# Sensor_Board_2_03_HX711_DS18b2.net
KiCad netlist of a schematic drawn in EAGLE
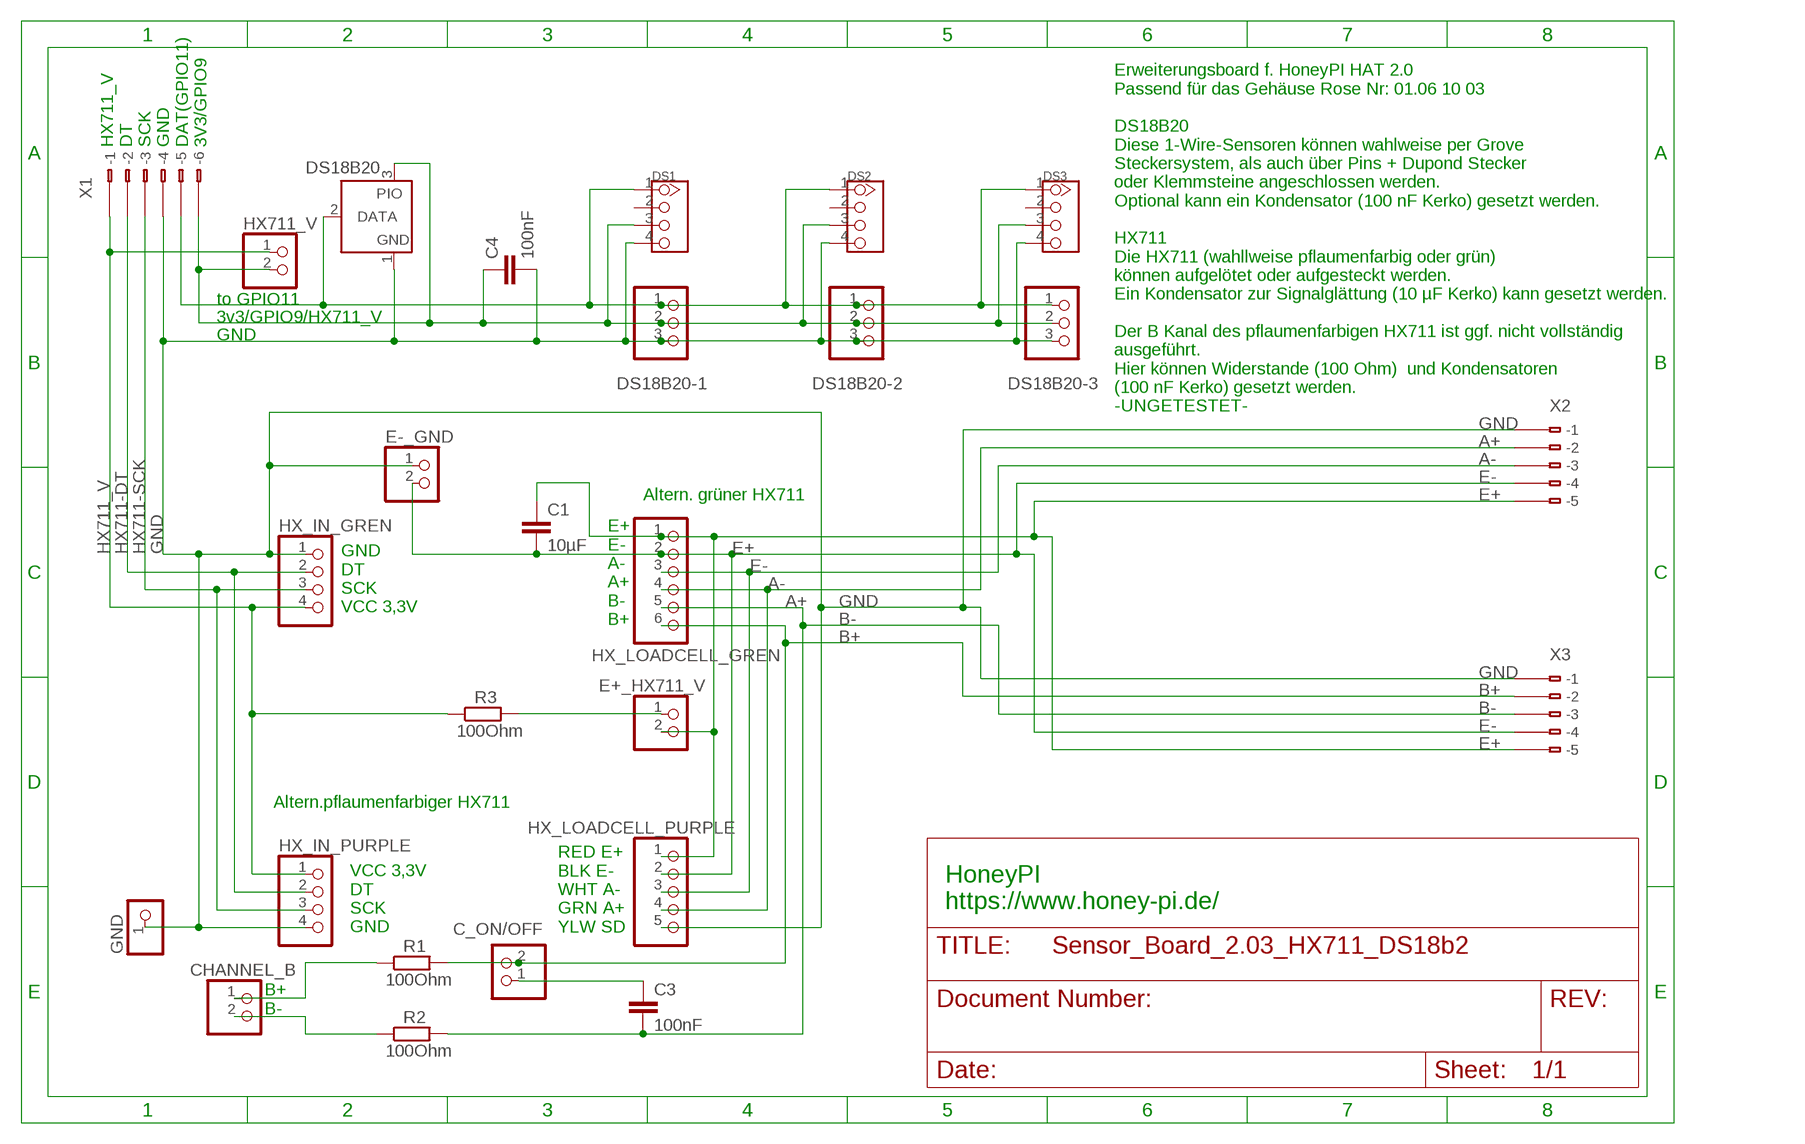
[diagram p0: schematic, sheet 1]

(export (version "E")
  (design (tool "Eeschema 10.0.6"))
  (components
    (comp (ref "C1")
      (value "10µF")
      (footprint "eagle-import:C5B2.5")
      (libsource (lib "eagle-import") (part "C5/2.5"))
    )
    (comp (ref "C3")
      (value "100nF")
      (footprint "eagle-import:C5B2.5")
      (libsource (lib "eagle-import") (part "C5/2.5"))
    )
    (comp (ref "C4")
      (value "100nF")
      (footprint "eagle-import:C5B2.5")
      (libsource (lib "eagle-import") (part "C5/2.5"))
    )
    (comp (ref "CHANNEL_B")
      (value "PINHD-1X2")
      (footprint "eagle-import:1X02")
      (libsource (lib "eagle-import") (part "PINHD-1X2"))
    )
    (comp (ref "C_ON/OFF")
      (value "PINHD-1X2")
      (footprint "eagle-import:1X02")
      (libsource (lib "eagle-import") (part "PINHD-1X2"))
    )
    (comp (ref "DS1")
      (value "TWIG-4P-2.0-2.0")
      (footprint "eagle-import:4P-2.0")
      (libsource (lib "eagle-import") (part "TWIG-4P-2.0-2.0"))
    )
    (comp (ref "DS2")
      (value "TWIG-4P-2.0-2.0")
      (footprint "eagle-import:4P-2.0")
      (libsource (lib "eagle-import") (part "TWIG-4P-2.0-2.0"))
    )
    (comp (ref "DS3")
      (value "TWIG-4P-2.0-2.0")
      (footprint "eagle-import:4P-2.0")
      (libsource (lib "eagle-import") (part "TWIG-4P-2.0-2.0"))
    )
    (comp (ref "DS18B20")
      (value "DS2405")
      (footprint "eagle-import:TO92-")
      (fields (field (name "MF") "DALLAS SEMICONDUCTOR"))
      (libsource (lib "eagle-import") (part "DS2405"))
    )
    (comp (ref "DS18B20-1")
      (value "PINHD-1X3")
      (footprint "eagle-import:1X03")
      (libsource (lib "eagle-import") (part "PINHD-1X3"))
    )
    (comp (ref "DS18B20-2")
      (value "PINHD-1X3")
      (footprint "eagle-import:1X03")
      (libsource (lib "eagle-import") (part "PINHD-1X3"))
    )
    (comp (ref "DS18B20-3")
      (value "PINHD-1X3")
      (footprint "eagle-import:1X03")
      (libsource (lib "eagle-import") (part "PINHD-1X3"))
    )
    (comp (ref "E+_HX711_V")
      (value "PINHD-1X2")
      (footprint "eagle-import:1X02")
      (libsource (lib "eagle-import") (part "PINHD-1X2"))
    )
    (comp (ref "E-_GND")
      (value "PINHD-1X2")
      (footprint "eagle-import:1X02")
      (libsource (lib "eagle-import") (part "PINHD-1X2"))
    )
    (comp (ref "GND")
      (value "PINHD-1X1")
      (footprint "eagle-import:1X01")
      (libsource (lib "eagle-import") (part "PINHD-1X1"))
    )
    (comp (ref "HX711_V")
      (value "PINHD-1X2")
      (footprint "eagle-import:1X02")
      (libsource (lib "eagle-import") (part "PINHD-1X2"))
    )
    (comp (ref "HX_IN_GREN")
      (value "PINHD-1X4")
      (footprint "eagle-import:1X04")
      (libsource (lib "eagle-import") (part "PINHD-1X4"))
    )
    (comp (ref "HX_IN_PURPLE")
      (value "PINHD-1X4")
      (footprint "eagle-import:1X04")
      (libsource (lib "eagle-import") (part "PINHD-1X4"))
    )
    (comp (ref "HX_LOADCELL_GREN")
      (value "PINHD-1X6")
      (footprint "eagle-import:1X06")
      (libsource (lib "eagle-import") (part "PINHD-1X6"))
    )
    (comp (ref "HX_LOADCELL_PURPLE")
      (value "PINHD-1X5")
      (footprint "eagle-import:1X05")
      (libsource (lib "eagle-import") (part "PINHD-1X5"))
    )
    (comp (ref "R1")
      (value "100Ohm")
      (footprint "eagle-import:0207_10")
      (libsource (lib "eagle-import") (part "R-EU_0207/10"))
    )
    (comp (ref "R2")
      (value "100Ohm")
      (footprint "eagle-import:0207_10")
      (libsource (lib "eagle-import") (part "R-EU_0207/10"))
    )
    (comp (ref "R3")
      (value "100Ohm")
      (footprint "eagle-import:0207_10")
      (libsource (lib "eagle-import") (part "R-EU_0207/10"))
    )
    (comp (ref "X1")
      (value "233-506")
      (footprint "eagle-import:233-506")
      (fields (field (name "MF") "Wago Corporation") (field (name "MPN") "0233-0506"))
      (libsource (lib "eagle-import") (part "233-506"))
    )
    (comp (ref "X2")
      (value "233-505")
      (footprint "eagle-import:233-505")
      (fields (field (name "MF") "Wago Corporation") (field (name "MPN") "0233-0505"))
      (libsource (lib "eagle-import") (part "233-505"))
    )
    (comp (ref "X3")
      (value "233-505")
      (footprint "eagle-import:233-505")
      (fields (field (name "MF") "Wago Corporation") (field (name "MPN") "0233-0505"))
      (libsource (lib "eagle-import") (part "233-505"))
    )
  )
  (nets
    (net (code "1") (name "/A+") (class "Default")
      (node (ref "HX_LOADCELL_GREN") (pin "4") (pinfunction "4_4") (pintype "passive"))
      (node (ref "HX_LOADCELL_PURPLE") (pin "4") (pinfunction "4_4") (pintype "passive"))
      (node (ref "X2") (pin "B2") (pinfunction "B-2_B2") (pintype "passive"))
    )
    (net (code "2") (name "/A-") (class "Default")
      (node (ref "HX_LOADCELL_GREN") (pin "3") (pinfunction "3_3") (pintype "passive"))
      (node (ref "HX_LOADCELL_PURPLE") (pin "3") (pinfunction "3_3") (pintype "passive"))
      (node (ref "X2") (pin "B3") (pinfunction "B-3_B3") (pintype "passive"))
    )
    (net (code "3") (name "/B+") (class "Default")
      (node (ref "C_ON/OFF") (pin "2") (pinfunction "2_2") (pintype "passive"))
      (node (ref "HX_LOADCELL_GREN") (pin "6") (pinfunction "6_6") (pintype "passive"))
      (node (ref "R1") (pin "2") (pinfunction "2_2") (pintype "passive"))
      (node (ref "X3") (pin "B2") (pinfunction "B-2_B2") (pintype "passive"))
    )
    (net (code "4") (name "/B-") (class "Default")
      (node (ref "C3") (pin "2") (pinfunction "2_2") (pintype "passive"))
      (node (ref "HX_LOADCELL_GREN") (pin "5") (pinfunction "5_5") (pintype "passive"))
      (node (ref "R2") (pin "2") (pinfunction "2_2") (pintype "passive"))
      (node (ref "X3") (pin "B3") (pinfunction "B-3_B3") (pintype "passive"))
    )
    (net (code "5") (name "/E+") (class "Default")
      (node (ref "C1") (pin "1") (pinfunction "1_1") (pintype "passive"))
      (node (ref "E+_HX711_V") (pin "2") (pinfunction "2_2") (pintype "passive"))
      (node (ref "HX_LOADCELL_GREN") (pin "1") (pinfunction "1_1") (pintype "passive"))
      (node (ref "HX_LOADCELL_PURPLE") (pin "1") (pinfunction "1_1") (pintype "passive"))
      (node (ref "X2") (pin "B5") (pinfunction "B-5_B5") (pintype "passive"))
      (node (ref "X3") (pin "B5") (pinfunction "B-5_B5") (pintype "passive"))
    )
    (net (code "6") (name "/E-") (class "Default")
      (node (ref "C1") (pin "2") (pinfunction "2_2") (pintype "passive"))
      (node (ref "E-_GND") (pin "2") (pinfunction "2_2") (pintype "passive"))
      (node (ref "HX_LOADCELL_GREN") (pin "2") (pinfunction "2_2") (pintype "passive"))
      (node (ref "HX_LOADCELL_PURPLE") (pin "2") (pinfunction "2_2") (pintype "passive"))
      (node (ref "X2") (pin "B4") (pinfunction "B-4_B4") (pintype "passive"))
      (node (ref "X3") (pin "B4") (pinfunction "B-4_B4") (pintype "passive"))
    )
    (net (code "7") (name "/GND") (class "Default")
      (node (ref "C4") (pin "2") (pinfunction "2_2") (pintype "passive"))
      (node (ref "DS1") (pin "4") (pinfunction "4_4") (pintype "bidirectional"))
      (node (ref "DS18B20") (pin "1") (pinfunction "GND_1") (pintype "passive"))
      (node (ref "DS18B20-1") (pin "3") (pinfunction "3_3") (pintype "passive"))
      (node (ref "DS18B20-2") (pin "3") (pinfunction "3_3") (pintype "passive"))
      (node (ref "DS18B20-3") (pin "3") (pinfunction "3_3") (pintype "passive"))
      (node (ref "DS2") (pin "4") (pinfunction "4_4") (pintype "bidirectional"))
      (node (ref "DS3") (pin "4") (pinfunction "4_4") (pintype "bidirectional"))
      (node (ref "E-_GND") (pin "1") (pinfunction "1_1") (pintype "passive"))
      (node (ref "GND") (pin "1") (pinfunction "1_1") (pintype "passive"))
      (node (ref "HX_IN_GREN") (pin "1") (pinfunction "1_1") (pintype "passive"))
      (node (ref "HX_IN_PURPLE") (pin "4") (pinfunction "4_4") (pintype "passive"))
      (node (ref "HX_LOADCELL_PURPLE") (pin "5") (pinfunction "5_5") (pintype "passive"))
      (node (ref "X1") (pin "B4") (pinfunction "B-4_B4") (pintype "passive"))
      (node (ref "X2") (pin "B1") (pinfunction "B-1_B1") (pintype "passive"))
      (node (ref "X3") (pin "B1") (pinfunction "B-1_B1") (pintype "passive"))
    )
    (net (code "8") (name "/HX711-DT") (class "Default")
      (node (ref "HX_IN_GREN") (pin "2") (pinfunction "2_2") (pintype "passive"))
      (node (ref "HX_IN_PURPLE") (pin "2") (pinfunction "2_2") (pintype "passive"))
      (node (ref "X1") (pin "B2") (pinfunction "B-2_B2") (pintype "passive"))
    )
    (net (code "9") (name "/HX711-SCK") (class "Default")
      (node (ref "HX_IN_GREN") (pin "3") (pinfunction "3_3") (pintype "passive"))
      (node (ref "HX_IN_PURPLE") (pin "3") (pinfunction "3_3") (pintype "passive"))
      (node (ref "X1") (pin "B3") (pinfunction "B-3_B3") (pintype "passive"))
    )
    (net (code "10") (name "/HX711_V") (class "Default")
      (node (ref "HX711_V") (pin "1") (pinfunction "1_1") (pintype "passive"))
      (node (ref "HX_IN_GREN") (pin "4") (pinfunction "4_4") (pintype "passive"))
      (node (ref "HX_IN_PURPLE") (pin "1") (pinfunction "1_1") (pintype "passive"))
      (node (ref "R3") (pin "1") (pinfunction "1_1") (pintype "passive"))
      (node (ref "X1") (pin "B1") (pinfunction "B-1_B1") (pintype "passive"))
    )
    (net (code "11") (name "Net-(C3-Pad1)") (class "Default")
      (node (ref "C3") (pin "1") (pinfunction "1_1") (pintype "passive"))
      (node (ref "C_ON/OFF") (pin "1") (pinfunction "1_1") (pintype "passive"))
    )
    (net (code "12") (name "Net-(CHANNEL_B-Pad1)") (class "Default")
      (node (ref "CHANNEL_B") (pin "1") (pinfunction "1_1") (pintype "passive"))
      (node (ref "R1") (pin "1") (pinfunction "1_1") (pintype "passive"))
    )
    (net (code "13") (name "Net-(CHANNEL_B-Pad2)") (class "Default")
      (node (ref "CHANNEL_B") (pin "2") (pinfunction "2_2") (pintype "passive"))
      (node (ref "R2") (pin "1") (pinfunction "1_1") (pintype "passive"))
    )
    (net (code "14") (name "Net-(DS18B20-DATA)") (class "Default")
      (node (ref "DS1") (pin "1") (pinfunction "1_1") (pintype "bidirectional"))
      (node (ref "DS18B20") (pin "2") (pinfunction "DATA_2") (pintype "input"))
      (node (ref "DS18B20-1") (pin "1") (pinfunction "1_1") (pintype "passive"))
      (node (ref "DS18B20-2") (pin "1") (pinfunction "1_1") (pintype "passive"))
      (node (ref "DS18B20-3") (pin "1") (pinfunction "1_1") (pintype "passive"))
      (node (ref "DS2") (pin "1") (pinfunction "1_1") (pintype "bidirectional"))
      (node (ref "DS3") (pin "1") (pinfunction "1_1") (pintype "bidirectional"))
      (node (ref "X1") (pin "B5") (pinfunction "B-5_B5") (pintype "passive"))
    )
    (net (code "15") (name "Net-(DS18B20-PIO)") (class "Default")
      (node (ref "C4") (pin "1") (pinfunction "1_1") (pintype "passive"))
      (node (ref "DS1") (pin "3") (pinfunction "3_3") (pintype "bidirectional"))
      (node (ref "DS18B20") (pin "3") (pinfunction "PIO_3") (pintype "passive"))
      (node (ref "DS18B20-1") (pin "2") (pinfunction "2_2") (pintype "passive"))
      (node (ref "DS18B20-2") (pin "2") (pinfunction "2_2") (pintype "passive"))
      (node (ref "DS18B20-3") (pin "2") (pinfunction "2_2") (pintype "passive"))
      (node (ref "DS2") (pin "3") (pinfunction "3_3") (pintype "bidirectional"))
      (node (ref "DS3") (pin "3") (pinfunction "3_3") (pintype "bidirectional"))
      (node (ref "HX711_V") (pin "2") (pinfunction "2_2") (pintype "passive"))
      (node (ref "X1") (pin "B6") (pinfunction "B-6_B6") (pintype "passive"))
    )
    (net (code "16") (name "Net-(E+_HX711_V-Pad1)") (class "Default")
      (node (ref "E+_HX711_V") (pin "1") (pinfunction "1_1") (pintype "passive"))
      (node (ref "R3") (pin "2") (pinfunction "2_2") (pintype "passive"))
    )
    (net (code "17") (name "unconnected-(DS1-Pad2)") (class "Default")
      (node (ref "DS1") (pin "2") (pinfunction "2_2") (pintype "bidirectional"))
    )
    (net (code "18") (name "unconnected-(DS2-Pad2)") (class "Default")
      (node (ref "DS2") (pin "2") (pinfunction "2_2") (pintype "bidirectional"))
    )
    (net (code "19") (name "unconnected-(DS3-Pad2)") (class "Default")
      (node (ref "DS3") (pin "2") (pinfunction "2_2") (pintype "bidirectional"))
    )
    (net (code "20") (name "unconnected-(X1--1-PadA1)") (class "Default")
      (node (ref "X1") (pin "A1") (pinfunction "-1_A1") (pintype "passive"))
    )
    (net (code "21") (name "unconnected-(X1--2-PadA2)") (class "Default")
      (node (ref "X1") (pin "A2") (pinfunction "-2_A2") (pintype "passive"))
    )
    (net (code "22") (name "unconnected-(X1--3-PadA3)") (class "Default")
      (node (ref "X1") (pin "A3") (pinfunction "-3_A3") (pintype "passive"))
    )
    (net (code "23") (name "unconnected-(X1--4-PadA4)") (class "Default")
      (node (ref "X1") (pin "A4") (pinfunction "-4_A4") (pintype "passive"))
    )
    (net (code "24") (name "unconnected-(X1--5-PadA5)") (class "Default")
      (node (ref "X1") (pin "A5") (pinfunction "-5_A5") (pintype "passive"))
    )
    (net (code "25") (name "unconnected-(X1--6-PadA6)") (class "Default")
      (node (ref "X1") (pin "A6") (pinfunction "-6_A6") (pintype "passive"))
    )
    (net (code "26") (name "unconnected-(X2--1-PadA1)") (class "Default")
      (node (ref "X2") (pin "A1") (pinfunction "-1_A1") (pintype "passive"))
    )
    (net (code "27") (name "unconnected-(X2--2-PadA2)") (class "Default")
      (node (ref "X2") (pin "A2") (pinfunction "-2_A2") (pintype "passive"))
    )
    (net (code "28") (name "unconnected-(X2--3-PadA3)") (class "Default")
      (node (ref "X2") (pin "A3") (pinfunction "-3_A3") (pintype "passive"))
    )
    (net (code "29") (name "unconnected-(X2--4-PadA4)") (class "Default")
      (node (ref "X2") (pin "A4") (pinfunction "-4_A4") (pintype "passive"))
    )
    (net (code "30") (name "unconnected-(X2--5-PadA5)") (class "Default")
      (node (ref "X2") (pin "A5") (pinfunction "-5_A5") (pintype "passive"))
    )
    (net (code "31") (name "unconnected-(X3--1-PadA1)") (class "Default")
      (node (ref "X3") (pin "A1") (pinfunction "-1_A1") (pintype "passive"))
    )
    (net (code "32") (name "unconnected-(X3--2-PadA2)") (class "Default")
      (node (ref "X3") (pin "A2") (pinfunction "-2_A2") (pintype "passive"))
    )
    (net (code "33") (name "unconnected-(X3--3-PadA3)") (class "Default")
      (node (ref "X3") (pin "A3") (pinfunction "-3_A3") (pintype "passive"))
    )
    (net (code "34") (name "unconnected-(X3--4-PadA4)") (class "Default")
      (node (ref "X3") (pin "A4") (pinfunction "-4_A4") (pintype "passive"))
    )
    (net (code "35") (name "unconnected-(X3--5-PadA5)") (class "Default")
      (node (ref "X3") (pin "A5") (pinfunction "-5_A5") (pintype "passive"))
    )
  )
)
